# Switch.net
KiCad netlist of a schematic drawn in Altium Designer
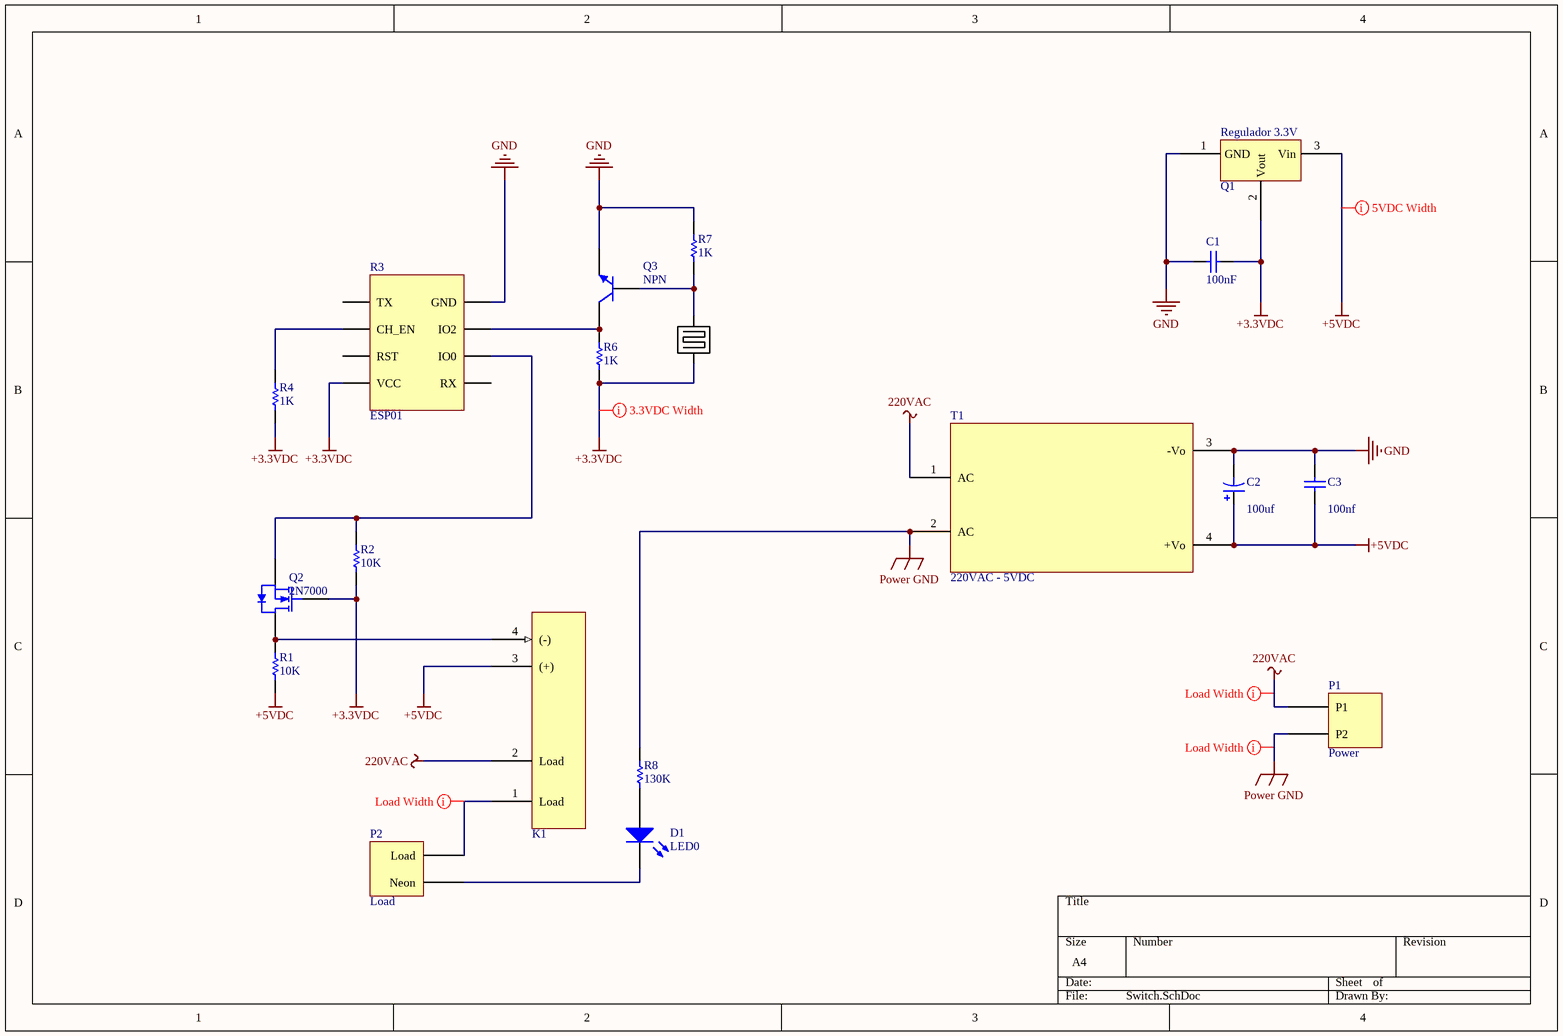
[diagram p0: Switch.SchDoc]

(export (version "E")
  (design (tool "Eeschema 10.0.6"))
  (components
    (comp (ref "C1")
      (value "100nF")
      (footprint "RAD-0.1")
      (description "Capacitor")
      (fields (field (name "Comment") "100nf") (field (name "PUBLISHER") "Altium Limited"))
      (libsource (lib "Miscellaneous Devices") (part "Cap"))
    )
    (comp (ref "C2")
      (value "100uf")
      (footprint "RAD-0.1")
      (description "Polarized Capacitor (Radial)")
      (fields (field (name "Comment") "Cap Pol1") (field (name "PUBLISHER") "Altium Limited"))
      (libsource (lib "Miscellaneous Devices") (part "Cap Pol1"))
    )
    (comp (ref "C3")
      (value "100nf")
      (footprint "RAD-0.1")
      (description "Capacitor")
      (fields (field (name "Comment") "Cap") (field (name "PUBLISHER") "Altium Limited"))
      (libsource (lib "Miscellaneous Devices") (part "Cap"))
    )
    (comp (ref "D1")
      (value "LED0")
      (footprint "Miscellaneous Devices PCB:RAD-0.1")
      (description "Typical INFRARED GaAs LED")
      (fields (field (name "PUBLISHER") "Altium Limited"))
      (libsource (lib "Miscellaneous Devices") (part "LED0"))
    )
    (comp (ref "K1")
      (value "G3MB-202P DC5")
      (footprint "G3MB-202P DC5")
      (description "RELAY MINI SSR 240VAC@2A ZERO")
      (fields (field (name "MFR") "Omron"))
      (libsource (lib "G3MB-202P") (part "G3MB-202P DC5"))
    )
    (comp (ref "P1")
      (value "Power")
      (footprint "ScrewTerminal-X2")
      (libsource (lib "") (part "ScrewTerminal_1"))
    )
    (comp (ref "P2")
      (value "Load")
      (footprint "ScrewTerminal-X2")
      (libsource (lib "ScrewTerminal_2X") (part "ScrewTerminal"))
    )
    (comp (ref "Q1")
      (value "Regulador 3.3V")
      (footprint "TO-220-AB")
      (libsource (lib "AMS1117") (part "AMS1117"))
    )
    (comp (ref "Q2")
      (value "2N7000")
      (footprint "Philips Footprints:SOT54")
      (description "N-channel Enhancement Mode Field-effect Transistor")
      (fields (field (name "PUBLISHER") "Altium Limited"))
      (libsource (lib "Philips Discrete MOSFET - Low Power") (part "2N7000"))
    )
    (comp (ref "Q3")
      (value "NPN")
      (footprint "Miscellaneous Devices:TO-92")
      (description "NPN Bipolar Transistor")
      (fields (field (name "PUBLISHER") "Altium Limited"))
      (libsource (lib "Miscellaneous Devices") (part "NPN"))
    )
    (comp (ref "R1")
      (value "10K")
      (footprint "AXIAL-0.3")
      (description "Resistor")
      (fields (field (name "PUBLISHER") "Altium Limited"))
      (libsource (lib "Miscellaneous Devices") (part "Res1"))
    )
    (comp (ref "R2")
      (value "10K")
      (footprint "AXIAL-0.3")
      (description "Resistor")
      (fields (field (name "PUBLISHER") "Altium Limited"))
      (libsource (lib "Miscellaneous Devices") (part "Res1"))
    )
    (comp (ref "R3") (value "ESP01") (footprint "HDR2X4") (libsource (lib "ESP01") (part "ESP01")))
    (comp (ref "R4")
      (value "1K")
      (footprint "AXIAL-0.3")
      (description "Resistor")
      (fields (field (name "Comment") "10K") (field (name "PUBLISHER") "Altium Limited"))
      (libsource (lib "Miscellaneous Devices") (part "Res1"))
    )
    (comp (ref "R5") (value "LDR") (footprint "RAD-0.1") (libsource (lib "LDR") (part "LDR")))
    (comp (ref "R6")
      (value "1K")
      (footprint "AXIAL-0.3")
      (description "Resistor")
      (fields (field (name "Comment") "10K") (field (name "PUBLISHER") "Altium Limited"))
      (libsource (lib "Miscellaneous Devices") (part "Res1"))
    )
    (comp (ref "R7")
      (value "1K")
      (footprint "AXIAL-0.3")
      (description "Resistor")
      (fields (field (name "Comment") "10K") (field (name "PUBLISHER") "Altium Limited"))
      (libsource (lib "Miscellaneous Devices") (part "Res1"))
    )
    (comp (ref "R8")
      (value "130K")
      (footprint "AXIAL-0.3")
      (description "Resistor")
      (fields (field (name "Comment") "10K") (field (name "PUBLISHER") "Altium Limited"))
      (libsource (lib "Miscellaneous Devices") (part "Res1"))
    )
    (comp (ref "T1")
      (value "220VAC - 5VDC")
      (footprint "HLK-PM")
      (description "HLK-PM*")
      (fields (field (name "MFR") "HLK-PM01"))
      (libsource (lib "HLK-PM") (part "HLK-PM"))
    )
  )
  (nets
    (net (code "1") (name "+3.3VDC") (class "Default")
      (node (ref "C1") (pin "2") (pinfunction "2_2") (pintype "passive"))
      (node (ref "Q1") (pin "2") (pinfunction "Vout_2") (pintype "passive"))
      (node (ref "Q2") (pin "2") (pinfunction "G_2") (pintype "passive"))
      (node (ref "R2") (pin "2") (pinfunction "2_2") (pintype "passive"))
      (node (ref "R3") (pin "4") (pinfunction "VCC_4") (pintype "passive"))
      (node (ref "R4") (pin "2") (pinfunction "2_2") (pintype "passive"))
      (node (ref "R5") (pin "2") (pintype "passive"))
      (node (ref "R6") (pin "2") (pinfunction "2_2") (pintype "passive"))
    )
    (net (code "2") (name "+5VDC") (class "Default")
      (node (ref "C2") (pin "1") (pinfunction "1_1") (pintype "passive"))
      (node (ref "C3") (pin "1") (pinfunction "1_1") (pintype "passive"))
      (node (ref "K1") (pin "3") (pinfunction "(+)_3") (pintype "power_in"))
      (node (ref "Q1") (pin "3") (pinfunction "Vin_3") (pintype "passive"))
      (node (ref "R1") (pin "2") (pinfunction "2_2") (pintype "passive"))
      (node (ref "T1") (pin "4") (pinfunction "+Vo_4") (pintype "passive"))
    )
    (net (code "3") (name "220VAC") (class "Default")
      (node (ref "K1") (pin "2") (pinfunction "Load_2") (pintype "passive"))
      (node (ref "P1") (pin "1") (pinfunction "P1_1") (pintype "passive"))
      (node (ref "T1") (pin "1") (pinfunction "AC_1") (pintype "power_in"))
    )
    (net (code "4") (name "GND") (class "Default")
      (node (ref "C1") (pin "1") (pinfunction "1_1") (pintype "passive"))
      (node (ref "C2") (pin "2") (pinfunction "2_2") (pintype "passive"))
      (node (ref "C3") (pin "2") (pinfunction "2_2") (pintype "passive"))
      (node (ref "Q1") (pin "1") (pinfunction "GND_1") (pintype "passive"))
      (node (ref "Q3") (pin "3") (pinfunction "E_3") (pintype "passive"))
      (node (ref "R3") (pin "5") (pinfunction "GND_5") (pintype "passive"))
      (node (ref "R7") (pin "2") (pinfunction "2_2") (pintype "passive"))
      (node (ref "T1") (pin "3") (pinfunction "-Vo_3") (pintype "passive"))
    )
    (net (code "5") (name "Net-(D1-A)") (class "Default")
      (node (ref "D1") (pin "1") (pinfunction "A_1") (pintype "passive"))
      (node (ref "R8") (pin "1") (pinfunction "1_1") (pintype "passive"))
    )
    (net (code "6") (name "Net-(D1-K)") (class "Default")
      (node (ref "D1") (pin "2") (pinfunction "K_2") (pintype "passive"))
      (node (ref "P2") (pin "1") (pinfunction "Neon_1") (pintype "passive"))
    )
    (net (code "7") (name "Net-(K1-(-))") (class "Default")
      (node (ref "K1") (pin "4") (pinfunction "(-)_4") (pintype "input"))
      (node (ref "Q2") (pin "1") (pinfunction "D_1") (pintype "passive"))
      (node (ref "R1") (pin "1") (pinfunction "1_1") (pintype "passive"))
    )
    (net (code "8") (name "Net-(P2-Load)") (class "Default")
      (node (ref "K1") (pin "1") (pinfunction "Load_1") (pintype "passive"))
      (node (ref "P2") (pin "2") (pinfunction "Load_2") (pintype "passive"))
    )
    (net (code "9") (name "Net-(Q2-S)") (class "Default")
      (node (ref "Q2") (pin "3") (pinfunction "S_3") (pintype "passive"))
      (node (ref "R2") (pin "1") (pinfunction "1_1") (pintype "passive"))
      (node (ref "R3") (pin "7") (pinfunction "IO0_7") (pintype "passive"))
    )
    (net (code "10") (name "Net-(Q3-B)") (class "Default")
      (node (ref "Q3") (pin "2") (pinfunction "B_2") (pintype "passive"))
      (node (ref "R5") (pin "1") (pintype "passive"))
      (node (ref "R7") (pin "1") (pinfunction "1_1") (pintype "passive"))
    )
    (net (code "11") (name "Net-(Q3-C)") (class "Default")
      (node (ref "Q3") (pin "1") (pinfunction "C_1") (pintype "passive"))
      (node (ref "R3") (pin "6") (pinfunction "IO2_6") (pintype "passive"))
      (node (ref "R6") (pin "1") (pinfunction "1_1") (pintype "passive"))
    )
    (net (code "12") (name "Net-(R3-CH_EN)") (class "Default")
      (node (ref "R3") (pin "2") (pinfunction "CH_EN_2") (pintype "passive"))
      (node (ref "R4") (pin "1") (pinfunction "1_1") (pintype "passive"))
    )
    (net (code "13") (name "Power GND") (class "Default")
      (node (ref "P1") (pin "2") (pinfunction "P2_2") (pintype "passive"))
      (node (ref "R8") (pin "2") (pinfunction "2_2") (pintype "passive"))
      (node (ref "T1") (pin "2") (pinfunction "AC_2") (pintype "power_in"))
    )
    (net (code "14") (name "unconnected-(R3-RST-Pad3)") (class "Default")
      (node (ref "R3") (pin "3") (pinfunction "RST_3") (pintype "passive"))
    )
    (net (code "15") (name "unconnected-(R3-RX-Pad8)") (class "Default")
      (node (ref "R3") (pin "8") (pinfunction "RX_8") (pintype "passive"))
    )
    (net (code "16") (name "unconnected-(R3-TX-Pad1)") (class "Default")
      (node (ref "R3") (pin "1") (pinfunction "TX_1") (pintype "passive"))
    )
  )
)
